# Active_noise_cancellation.net
KiCad netlist of a schematic drawn in EAGLE
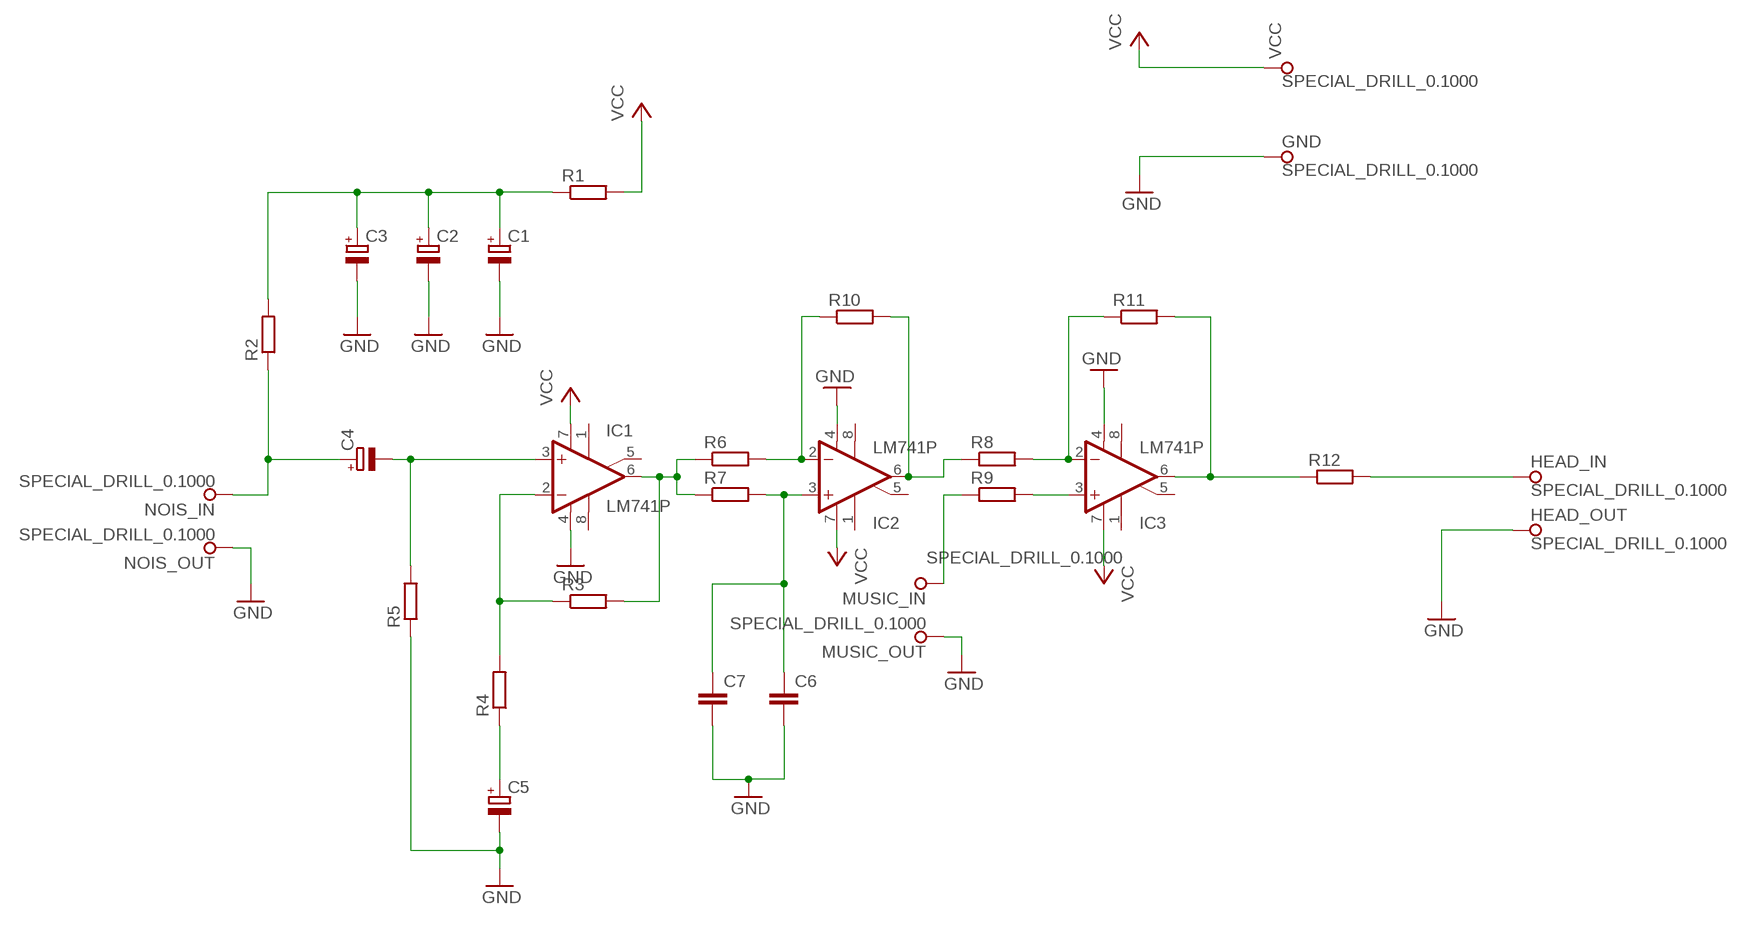
[diagram p0: schematic, sheet 1]

(export (version "E")
  (design (tool "Eeschema 10.0.6"))
  (components
    (comp (ref "C1")
      (value "CPOL-EUE1.8-4")
      (footprint "eagle-import:E1,8-4")
      (libsource (lib "eagle-import") (part "CPOL-EUE1.8-4"))
    )
    (comp (ref "C2")
      (value "CPOL-EUE1.8-4")
      (footprint "eagle-import:E1,8-4")
      (libsource (lib "eagle-import") (part "CPOL-EUE1.8-4"))
    )
    (comp (ref "C3")
      (value "CPOL-EUE1.8-4")
      (footprint "eagle-import:E1,8-4")
      (libsource (lib "eagle-import") (part "CPOL-EUE1.8-4"))
    )
    (comp (ref "C4")
      (value "CPOL-EUE1.8-4")
      (footprint "eagle-import:E1,8-4")
      (libsource (lib "eagle-import") (part "CPOL-EUE1.8-4"))
    )
    (comp (ref "C5")
      (value "CPOL-EUE1.8-4")
      (footprint "eagle-import:E1,8-4")
      (libsource (lib "eagle-import") (part "CPOL-EUE1.8-4"))
    )
    (comp (ref "C6")
      (value "C-EU050-024X044")
      (footprint "eagle-import:C050-024X044")
      (libsource (lib "eagle-import") (part "C-EU050-024X044"))
    )
    (comp (ref "C7")
      (value "C-EU050-024X044")
      (footprint "eagle-import:C050-024X044")
      (libsource (lib "eagle-import") (part "C-EU050-024X044"))
    )
    (comp (ref "GND")
      (value "SPECIAL_DRILL_0.1000")
      (footprint "eagle-import:PAD_0.1000")
      (libsource (lib "eagle-import") (part "SPECIAL_DRILL_0.1000"))
    )
    (comp (ref "HEAD_IN")
      (value "SPECIAL_DRILL_0.1000")
      (footprint "eagle-import:PAD_0.1000")
      (libsource (lib "eagle-import") (part "SPECIAL_DRILL_0.1000"))
    )
    (comp (ref "HEAD_OUT")
      (value "SPECIAL_DRILL_0.1000")
      (footprint "eagle-import:PAD_0.1000")
      (libsource (lib "eagle-import") (part "SPECIAL_DRILL_0.1000"))
    )
    (comp (ref "IC1")
      (value "LM741P")
      (footprint "eagle-import:DIL08")
      (libsource (lib "eagle-import") (part "741PLM"))
    )
    (comp (ref "IC2")
      (value "LM741P")
      (footprint "eagle-import:DIL08")
      (libsource (lib "eagle-import") (part "741PLM"))
    )
    (comp (ref "IC3")
      (value "LM741P")
      (footprint "eagle-import:DIL08")
      (libsource (lib "eagle-import") (part "741PLM"))
    )
    (comp (ref "MUSIC_IN")
      (value "SPECIAL_DRILL_0.1000")
      (footprint "eagle-import:PAD_0.1000")
      (libsource (lib "eagle-import") (part "SPECIAL_DRILL_0.1000"))
    )
    (comp (ref "MUSIC_OUT")
      (value "SPECIAL_DRILL_0.1000")
      (footprint "eagle-import:PAD_0.1000")
      (libsource (lib "eagle-import") (part "SPECIAL_DRILL_0.1000"))
    )
    (comp (ref "NOIS_IN")
      (value "SPECIAL_DRILL_0.1000")
      (footprint "eagle-import:PAD_0.1000")
      (libsource (lib "eagle-import") (part "SPECIAL_DRILL_0.1000"))
    )
    (comp (ref "NOIS_OUT")
      (value "SPECIAL_DRILL_0.1000")
      (footprint "eagle-import:PAD_0.1000")
      (libsource (lib "eagle-import") (part "SPECIAL_DRILL_0.1000"))
    )
    (comp (ref "R1")
      (value "R-EU_0204/7")
      (footprint "eagle-import:0204_7")
      (libsource (lib "eagle-import") (part "R-EU_0204/7"))
    )
    (comp (ref "R2")
      (value "R-EU_0204/7")
      (footprint "eagle-import:0204_7")
      (libsource (lib "eagle-import") (part "R-EU_0204/7"))
    )
    (comp (ref "R3")
      (value "R-EU_0204/7")
      (footprint "eagle-import:0204_7")
      (libsource (lib "eagle-import") (part "R-EU_0204/7"))
    )
    (comp (ref "R4")
      (value "R-EU_0204/7")
      (footprint "eagle-import:0204_7")
      (libsource (lib "eagle-import") (part "R-EU_0204/7"))
    )
    (comp (ref "R5")
      (value "R-EU_0204/7")
      (footprint "eagle-import:0204_7")
      (libsource (lib "eagle-import") (part "R-EU_0204/7"))
    )
    (comp (ref "R6")
      (value "R-EU_0204/7")
      (footprint "eagle-import:0204_7")
      (libsource (lib "eagle-import") (part "R-EU_0204/7"))
    )
    (comp (ref "R7")
      (value "R-EU_0204/7")
      (footprint "eagle-import:0204_7")
      (libsource (lib "eagle-import") (part "R-EU_0204/7"))
    )
    (comp (ref "R8")
      (value "R-EU_0204/7")
      (footprint "eagle-import:0204_7")
      (libsource (lib "eagle-import") (part "R-EU_0204/7"))
    )
    (comp (ref "R9")
      (value "R-EU_0204/7")
      (footprint "eagle-import:0204_7")
      (libsource (lib "eagle-import") (part "R-EU_0204/7"))
    )
    (comp (ref "R10")
      (value "R-EU_0204/7")
      (footprint "eagle-import:0204_7")
      (libsource (lib "eagle-import") (part "R-EU_0204/7"))
    )
    (comp (ref "R11")
      (value "R-EU_0204/7")
      (footprint "eagle-import:0204_7")
      (libsource (lib "eagle-import") (part "R-EU_0204/7"))
    )
    (comp (ref "R12")
      (value "R-EU_0204/7")
      (footprint "eagle-import:0204_7")
      (libsource (lib "eagle-import") (part "R-EU_0204/7"))
    )
    (comp (ref "VCC")
      (value "SPECIAL_DRILL_0.1000")
      (footprint "eagle-import:PAD_0.1000")
      (libsource (lib "eagle-import") (part "SPECIAL_DRILL_0.1000"))
    )
  )
  (nets
    (net (code "1") (name "GND") (class "Default")
      (node (ref "C1") (pin "-") (pinfunction "-_-") (pintype "passive"))
      (node (ref "C2") (pin "-") (pinfunction "-_-") (pintype "passive"))
      (node (ref "C3") (pin "-") (pinfunction "-_-") (pintype "passive"))
      (node (ref "C5") (pin "-") (pinfunction "-_-") (pintype "passive"))
      (node (ref "C6") (pin "2") (pinfunction "2_2") (pintype "passive"))
      (node (ref "C7") (pin "2") (pinfunction "2_2") (pintype "passive"))
      (node (ref "GND") (pin "1") (pinfunction "1_1") (pintype "passive"))
      (node (ref "HEAD_OUT") (pin "1") (pinfunction "1_1") (pintype "passive"))
      (node (ref "IC1") (pin "4") (pinfunction "V-_4") (pintype "power_in"))
      (node (ref "IC2") (pin "4") (pinfunction "V-_4") (pintype "power_in"))
      (node (ref "IC3") (pin "4") (pinfunction "V-_4") (pintype "power_in"))
      (node (ref "MUSIC_OUT") (pin "1") (pinfunction "1_1") (pintype "passive"))
      (node (ref "NOIS_OUT") (pin "1") (pinfunction "1_1") (pintype "passive"))
      (node (ref "R5") (pin "1") (pinfunction "1_1") (pintype "passive"))
    )
    (net (code "2") (name "Net-(C1-Pad+)") (class "Default")
      (node (ref "C1") (pin "+") (pinfunction "+_+") (pintype "passive"))
      (node (ref "C2") (pin "+") (pinfunction "+_+") (pintype "passive"))
      (node (ref "C3") (pin "+") (pinfunction "+_+") (pintype "passive"))
      (node (ref "R1") (pin "1") (pinfunction "1_1") (pintype "passive"))
      (node (ref "R2") (pin "2") (pinfunction "2_2") (pintype "passive"))
    )
    (net (code "3") (name "Net-(C4-Pad+)") (class "Default")
      (node (ref "C4") (pin "+") (pinfunction "+_+") (pintype "passive"))
      (node (ref "NOIS_IN") (pin "1") (pinfunction "1_1") (pintype "passive"))
      (node (ref "R2") (pin "1") (pinfunction "1_1") (pintype "passive"))
    )
    (net (code "4") (name "Net-(C5-Pad+)") (class "Default")
      (node (ref "C5") (pin "+") (pinfunction "+_+") (pintype "passive"))
      (node (ref "R4") (pin "1") (pinfunction "1_1") (pintype "passive"))
    )
    (net (code "5") (name "Net-(HEAD_IN-Pad1)") (class "Default")
      (node (ref "HEAD_IN") (pin "1") (pinfunction "1_1") (pintype "passive"))
      (node (ref "R12") (pin "2") (pinfunction "2_2") (pintype "passive"))
    )
    (net (code "6") (name "Net-(IC1-+IN)") (class "Default")
      (node (ref "C4") (pin "-") (pinfunction "-_-") (pintype "passive"))
      (node (ref "IC1") (pin "3") (pinfunction "+IN_3") (pintype "input"))
      (node (ref "R5") (pin "2") (pinfunction "2_2") (pintype "passive"))
    )
    (net (code "7") (name "Net-(IC1--IN)") (class "Default")
      (node (ref "IC1") (pin "2") (pinfunction "-IN_2") (pintype "input"))
      (node (ref "R3") (pin "1") (pinfunction "1_1") (pintype "passive"))
      (node (ref "R4") (pin "2") (pinfunction "2_2") (pintype "passive"))
    )
    (net (code "8") (name "Net-(IC1-OUT)") (class "Default")
      (node (ref "IC1") (pin "6") (pinfunction "OUT_6") (pintype "output"))
      (node (ref "R3") (pin "2") (pinfunction "2_2") (pintype "passive"))
      (node (ref "R6") (pin "1") (pinfunction "1_1") (pintype "passive"))
      (node (ref "R7") (pin "1") (pinfunction "1_1") (pintype "passive"))
    )
    (net (code "9") (name "Net-(IC2-+IN)") (class "Default")
      (node (ref "C6") (pin "1") (pinfunction "1_1") (pintype "passive"))
      (node (ref "C7") (pin "1") (pinfunction "1_1") (pintype "passive"))
      (node (ref "IC2") (pin "3") (pinfunction "+IN_3") (pintype "input"))
      (node (ref "R7") (pin "2") (pinfunction "2_2") (pintype "passive"))
    )
    (net (code "10") (name "Net-(IC2--IN)") (class "Default")
      (node (ref "IC2") (pin "2") (pinfunction "-IN_2") (pintype "input"))
      (node (ref "R10") (pin "1") (pinfunction "1_1") (pintype "passive"))
      (node (ref "R6") (pin "2") (pinfunction "2_2") (pintype "passive"))
    )
    (net (code "11") (name "Net-(IC2-OUT)") (class "Default")
      (node (ref "IC2") (pin "6") (pinfunction "OUT_6") (pintype "output"))
      (node (ref "R10") (pin "2") (pinfunction "2_2") (pintype "passive"))
      (node (ref "R8") (pin "1") (pinfunction "1_1") (pintype "passive"))
    )
    (net (code "12") (name "Net-(IC3-+IN)") (class "Default")
      (node (ref "IC3") (pin "3") (pinfunction "+IN_3") (pintype "input"))
      (node (ref "R9") (pin "2") (pinfunction "2_2") (pintype "passive"))
    )
    (net (code "13") (name "Net-(IC3--IN)") (class "Default")
      (node (ref "IC3") (pin "2") (pinfunction "-IN_2") (pintype "input"))
      (node (ref "R11") (pin "1") (pinfunction "1_1") (pintype "passive"))
      (node (ref "R8") (pin "2") (pinfunction "2_2") (pintype "passive"))
    )
    (net (code "14") (name "Net-(IC3-OUT)") (class "Default")
      (node (ref "IC3") (pin "6") (pinfunction "OUT_6") (pintype "output"))
      (node (ref "R11") (pin "2") (pinfunction "2_2") (pintype "passive"))
      (node (ref "R12") (pin "1") (pinfunction "1_1") (pintype "passive"))
    )
    (net (code "15") (name "Net-(MUSIC_IN-Pad1)") (class "Default")
      (node (ref "MUSIC_IN") (pin "1") (pinfunction "1_1") (pintype "passive"))
      (node (ref "R9") (pin "1") (pinfunction "1_1") (pintype "passive"))
    )
    (net (code "16") (name "VCC") (class "Default")
      (node (ref "IC1") (pin "7") (pinfunction "V+_7") (pintype "power_in"))
      (node (ref "IC2") (pin "7") (pinfunction "V+_7") (pintype "power_in"))
      (node (ref "IC3") (pin "7") (pinfunction "V+_7") (pintype "power_in"))
      (node (ref "R1") (pin "2") (pinfunction "2_2") (pintype "passive"))
      (node (ref "VCC") (pin "1") (pinfunction "1_1") (pintype "passive"))
    )
    (net (code "17") (name "unconnected-(IC1-ON1-Pad1)") (class "Default")
      (node (ref "IC1") (pin "1") (pinfunction "ON1_1") (pintype "passive"))
    )
    (net (code "18") (name "unconnected-(IC1-ON2-Pad5)") (class "Default")
      (node (ref "IC1") (pin "5") (pinfunction "ON2_5") (pintype "passive"))
    )
    (net (code "19") (name "unconnected-(IC1-OPT-Pad8)") (class "Default")
      (node (ref "IC1") (pin "8") (pinfunction "OPT_8") (pintype "passive"))
    )
    (net (code "20") (name "unconnected-(IC2-ON1-Pad1)") (class "Default")
      (node (ref "IC2") (pin "1") (pinfunction "ON1_1") (pintype "passive"))
    )
    (net (code "21") (name "unconnected-(IC2-ON2-Pad5)") (class "Default")
      (node (ref "IC2") (pin "5") (pinfunction "ON2_5") (pintype "passive"))
    )
    (net (code "22") (name "unconnected-(IC2-OPT-Pad8)") (class "Default")
      (node (ref "IC2") (pin "8") (pinfunction "OPT_8") (pintype "passive"))
    )
    (net (code "23") (name "unconnected-(IC3-ON1-Pad1)") (class "Default")
      (node (ref "IC3") (pin "1") (pinfunction "ON1_1") (pintype "passive"))
    )
    (net (code "24") (name "unconnected-(IC3-ON2-Pad5)") (class "Default")
      (node (ref "IC3") (pin "5") (pinfunction "ON2_5") (pintype "passive"))
    )
    (net (code "25") (name "unconnected-(IC3-OPT-Pad8)") (class "Default")
      (node (ref "IC3") (pin "8") (pinfunction "OPT_8") (pintype "passive"))
    )
  )
)
